# power.net
KiCad netlist of a schematic drawn in Altium Designer
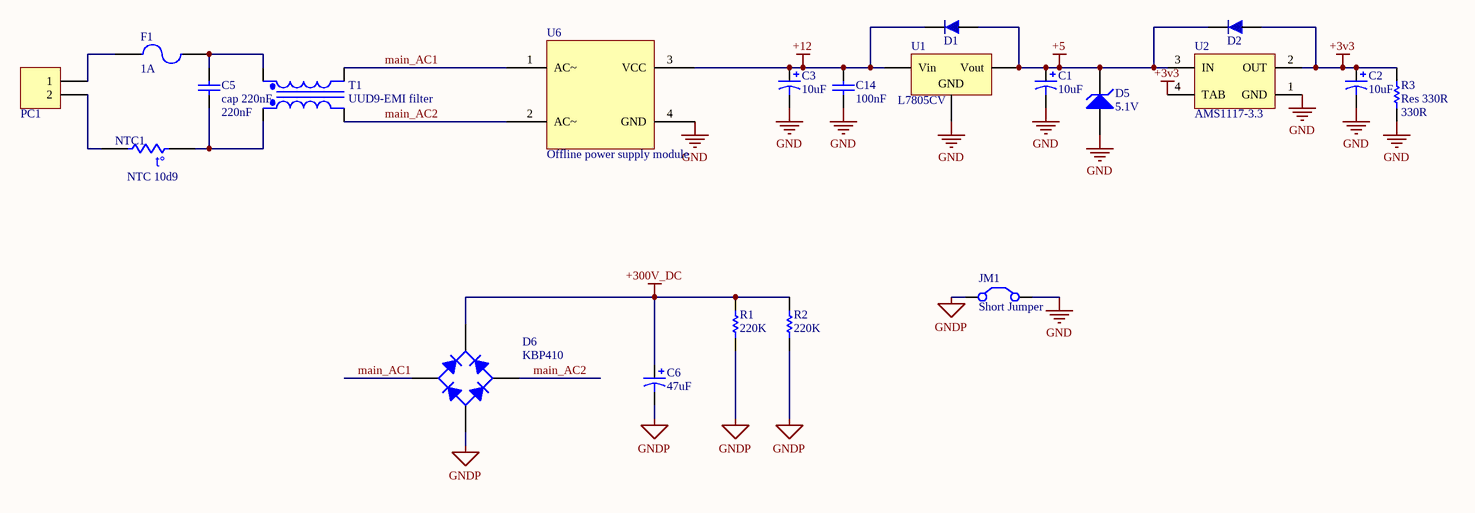
[diagram p0: power.SchDoc]

(export (version "E")
  (design (tool "Eeschema 10.0.6"))
  (components
    (comp (ref "C1")
      (value "10uF")
      (footprint "CAP0805")
      (description "CAP seramic")
      (fields (field (name "Comment") "cap 10uF") (field (name "PUBLISHER") "Altium Limited"))
      (libsource (lib "Miscellaneous Devices") (part "Cap Pol1"))
    )
    (comp (ref "C2")
      (value "10uF")
      (footprint "CAP0805")
      (description "CAP seramic")
      (fields (field (name "Comment") "cap 10uF") (field (name "PUBLISHER") "Altium Limited"))
      (libsource (lib "Miscellaneous Devices") (part "Cap Pol1"))
    )
    (comp (ref "C3")
      (value "10uF")
      (footprint "CAP0805")
      (description "CAP seramic")
      (fields (field (name "Comment") "cap 10uF") (field (name "PUBLISHER") "Altium Limited"))
      (libsource (lib "Miscellaneous Devices") (part "Cap Pol1"))
    )
    (comp (ref "C5")
      (value "cap 220nF")
      (footprint "MKT-15mm")
      (description "Cap MKT 275V")
      (fields (field (name "ALTIUM_VALUE") "220nF") (field (name "PUBLISHER") "Altium Limited"))
      (libsource (lib "Miscellaneous Devices") (part "Cap"))
    )
    (comp (ref "C6")
      (value "47uF")
      (footprint "ESP8266-12E_ESP-12E:Cap16MM")
      (description "Polarized Capacitor (Radial) 400V")
      (fields (field (name "Comment") "cap 47uF") (field (name "PUBLISHER") "Altium Limited"))
      (libsource (lib "Miscellaneous Devices") (part "Cap Pol1"))
    )
    (comp (ref "C14")
      (value "100nF")
      (footprint "CAP0805")
      (description "CAP seramic")
      (fields (field (name "Comment") "cap 100nF"))
      (libsource (lib "Altium library (www.AVRelec.com)") (part "Cap ceramic"))
    )
    (comp (ref "D1")
      (value "uf4007")
      (footprint "DIOM4629X24N")
      (description "Standard Rectifiers")
      (fields (field (name "MANUFACTURER") "DC COMPONENTS") (field (name "DESIGNER") "Abbas Basereh"))
      (libsource (lib "Altium (2)") (part "1n4007 SMD M7"))
    )
    (comp (ref "D2")
      (value "uf4007")
      (footprint "DIOM4629X24N")
      (description "Standard Rectifiers")
      (fields (field (name "MANUFACTURER") "DC COMPONENTS") (field (name "DESIGNER") "Abbas Basereh"))
      (libsource (lib "Altium (2)") (part "1n4007 SMD M7"))
    )
    (comp (ref "D5")
      (value "5.1V")
      (footprint "Diode 1n4148 SMD")
      (description "Zener Diode")
      (fields (field (name "PUBLISHER") "Altium Limited"))
      (libsource (lib "Miscellaneous Devices") (part "D Zener"))
    )
    (comp (ref "D6")
      (value "KBP410")
      (footprint "Bridge KBL PACKAGE")
      (description "Diode Bridge")
      (libsource (lib "Altium") (part "Diode Bridge"))
    )
    (comp (ref "F1")
      (value "1A")
      (footprint "PIN-W2/E2.8")
      (description "Fuse")
      (fields (field (name "PUBLISHER") "Altium Limited"))
      (libsource (lib "Miscellaneous Devices") (part "Fuse 2"))
    )
    (comp (ref "JM1")
      (value "Short Jumper")
      (footprint "short_bridge")
      (description "short circuit")
      (libsource (lib "common") (part "Solder Jumper"))
    )
    (comp (ref "NTC1")
      (value "NTC 10d9")
      (footprint "CAPNTO5.08-7.37x3.94")
      (description "NTC")
      (fields (field (name "PUBLISHER") "Altium Limited"))
      (libsource (lib "Miscellaneous Devices") (part "Res Thermal"))
    )
    (comp (ref "PC1")
      (value "Power Connector")
      (footprint "phoenix terminal R 2")
      (description "white Power Connector")
      (libsource (lib "Altium library (www.AVRelec.com)") (part "Power Connector"))
    )
    (comp (ref "R1")
      (value "220K")
      (footprint "RES-(1/2)-Stand")
      (description "Resistor")
      (fields (field (name "Comment") "Res 220K") (field (name "PUBLISHER") "Altium Limited"))
      (libsource (lib "Miscellaneous Devices") (part "Res1"))
    )
    (comp (ref "R2")
      (value "220K")
      (footprint "RES-(1/2)-Stand")
      (description "Resistor")
      (fields (field (name "Comment") "Res 220K") (field (name "PUBLISHER") "Altium Limited"))
      (libsource (lib "Miscellaneous Devices") (part "Res1"))
    )
    (comp (ref "R3")
      (value "Res 330R")
      (footprint "RES0805")
      (description "Resistor")
      (fields (field (name "ALTIUM_VALUE") "330R") (field (name "PUBLISHER") "Altium Limited"))
      (libsource (lib "Miscellaneous Devices") (part "Res1"))
    )
    (comp (ref "T1")
      (value "UUD9-EMI filter")
      (footprint "UUD9.8")
      (description "Line filter")
      (fields (field (name "PUBLISHER") "Altium Limited"))
      (libsource (lib "Miscellaneous Devices") (part "Trans Cupl"))
    )
    (comp (ref "U1")
      (value "L7805CV")
      (footprint "REG-7805-smd")
      (description "Linear Voltage Regulator IC Positive FIXED")
      (fields (field (name "MANUFACTURER") "STMicroelectronics") (field (name "DESIGNER") "Abbas Basereh"))
      (libsource (lib "Altium (2)") (part "L7805CV-Linear Voltage Regulator IC Positive 1 Output 5V 1.5A TO-220AB"))
    )
    (comp (ref "U2")
      (value "AMS1117-3.3")
      (footprint "SOT223")
      (description "x.x Volt, 800mA Low-Dropout Linear Regulator, 4-pin SOT-223")
      (fields (field (name "DESIGNER") "Ali Hafizi"))
      (libsource (lib "Altium (2)") (part "AMS1117-x.x"))
    )
    (comp (ref "U6")
      (value "Offline power supply module")
      (footprint "220AC-12VDC  450mA")
      (libsource (lib "Schlib1") (part "Power Supply Module"))
    )
  )
  (nets
    (net (code "1") (name "+3v3") (class "Default")
      (node (ref "C2") (pin "1") (pinfunction "1_1") (pintype "passive"))
      (node (ref "D2") (pin "1") (pintype "passive"))
      (node (ref "R3") (pin "2") (pinfunction "2_2") (pintype "passive"))
      (node (ref "U2") (pin "2") (pinfunction "OUT_2") (pintype "power_in"))
      (node (ref "U2") (pin "4") (pinfunction "TAB_4") (pintype "power_in"))
    )
    (net (code "2") (name "+5") (class "Default")
      (node (ref "C1") (pin "1") (pinfunction "1_1") (pintype "passive"))
      (node (ref "D1") (pin "1") (pintype "passive"))
      (node (ref "D2") (pin "2") (pintype "passive"))
      (node (ref "D5") (pin "2") (pinfunction "K_2") (pintype "passive"))
      (node (ref "U1") (pin "3") (pinfunction "Vout_3") (pintype "passive"))
      (node (ref "U2") (pin "3") (pinfunction "IN_3") (pintype "power_in"))
    )
    (net (code "3") (name "+12") (class "Default")
      (node (ref "C14") (pin "1") (pinfunction "1_1") (pintype "passive"))
      (node (ref "C3") (pin "1") (pinfunction "1_1") (pintype "passive"))
      (node (ref "D1") (pin "2") (pintype "passive"))
      (node (ref "U1") (pin "1") (pinfunction "Vin_1") (pintype "passive"))
      (node (ref "U6") (pin "3") (pinfunction "VCC_3") (pintype "power_in"))
    )
    (net (code "4") (name "+300V_DC") (class "Default")
      (node (ref "C6") (pin "1") (pinfunction "1_1") (pintype "passive"))
      (node (ref "D6") (pin "1") (pinfunction "K_1") (pintype "passive"))
      (node (ref "R1") (pin "2") (pinfunction "2_2") (pintype "passive"))
      (node (ref "R2") (pin "2") (pinfunction "2_2") (pintype "passive"))
    )
    (net (code "5") (name "/main_AC1") (class "Default")
      (node (ref "D6") (pin "4") (pinfunction "C_4") (pintype "passive"))
      (node (ref "T1") (pin "4") (pinfunction "Sec-_4") (pintype "passive"))
      (node (ref "U6") (pin "1") (pinfunction "AC~_1") (pintype "power_in"))
    )
    (net (code "6") (name "/main_AC2") (class "Default")
      (node (ref "D6") (pin "2") (pinfunction "C_2") (pintype "passive"))
      (node (ref "T1") (pin "2") (pinfunction "Pri-_2") (pintype "passive"))
      (node (ref "U6") (pin "2") (pinfunction "AC~_2") (pintype "power_in"))
    )
    (net (code "7") (name "GND") (class "Default")
      (node (ref "C1") (pin "2") (pinfunction "2_2") (pintype "passive"))
      (node (ref "C14") (pin "2") (pinfunction "2_2") (pintype "passive"))
      (node (ref "C2") (pin "2") (pinfunction "2_2") (pintype "passive"))
      (node (ref "C3") (pin "2") (pinfunction "2_2") (pintype "passive"))
      (node (ref "D5") (pin "1") (pinfunction "A_1") (pintype "passive"))
      (node (ref "JM1") (pin "2") (pinfunction "2_2") (pintype "passive"))
      (node (ref "R3") (pin "1") (pinfunction "1_1") (pintype "passive"))
      (node (ref "U1") (pin "2") (pinfunction "GND_2") (pintype "passive"))
      (node (ref "U2") (pin "1") (pinfunction "GND_1") (pintype "power_in"))
      (node (ref "U6") (pin "4") (pinfunction "GND_4") (pintype "power_in"))
    )
    (net (code "8") (name "GNDP") (class "Default")
      (node (ref "C6") (pin "2") (pinfunction "2_2") (pintype "passive"))
      (node (ref "D6") (pin "3") (pinfunction "A_3") (pintype "passive"))
      (node (ref "JM1") (pin "1") (pinfunction "1_1") (pintype "passive"))
      (node (ref "R1") (pin "1") (pinfunction "1_1") (pintype "passive"))
      (node (ref "R2") (pin "1") (pinfunction "1_1") (pintype "passive"))
    )
    (net (code "9") (name "Net-(F1-Pad1)") (class "Default")
      (node (ref "F1") (pin "1") (pinfunction "1_1") (pintype "passive"))
      (node (ref "PC1") (pin "1") (pinfunction "1_1") (pintype "passive"))
    )
    (net (code "10") (name "Net-(NTC1-Pad2)") (class "Default")
      (node (ref "NTC1") (pin "2") (pinfunction "2_2") (pintype "passive"))
      (node (ref "PC1") (pin "2") (pinfunction "2_2") (pintype "passive"))
    )
    (net (code "11") (name "Net-(T1-Pri+)") (class "Default")
      (node (ref "C5") (pin "1") (pinfunction "1_1") (pintype "passive"))
      (node (ref "NTC1") (pin "1") (pinfunction "1_1") (pintype "passive"))
      (node (ref "T1") (pin "1") (pinfunction "Pri+_1") (pintype "passive"))
    )
    (net (code "12") (name "Net-(T1-Sec+)") (class "Default")
      (node (ref "C5") (pin "2") (pinfunction "2_2") (pintype "passive"))
      (node (ref "F1") (pin "2") (pinfunction "2_2") (pintype "passive"))
      (node (ref "T1") (pin "3") (pinfunction "Sec+_3") (pintype "passive"))
    )
  )
)
